# VA-Meter_Analog_Part.net
KiCad netlist of a schematic drawn in EAGLE
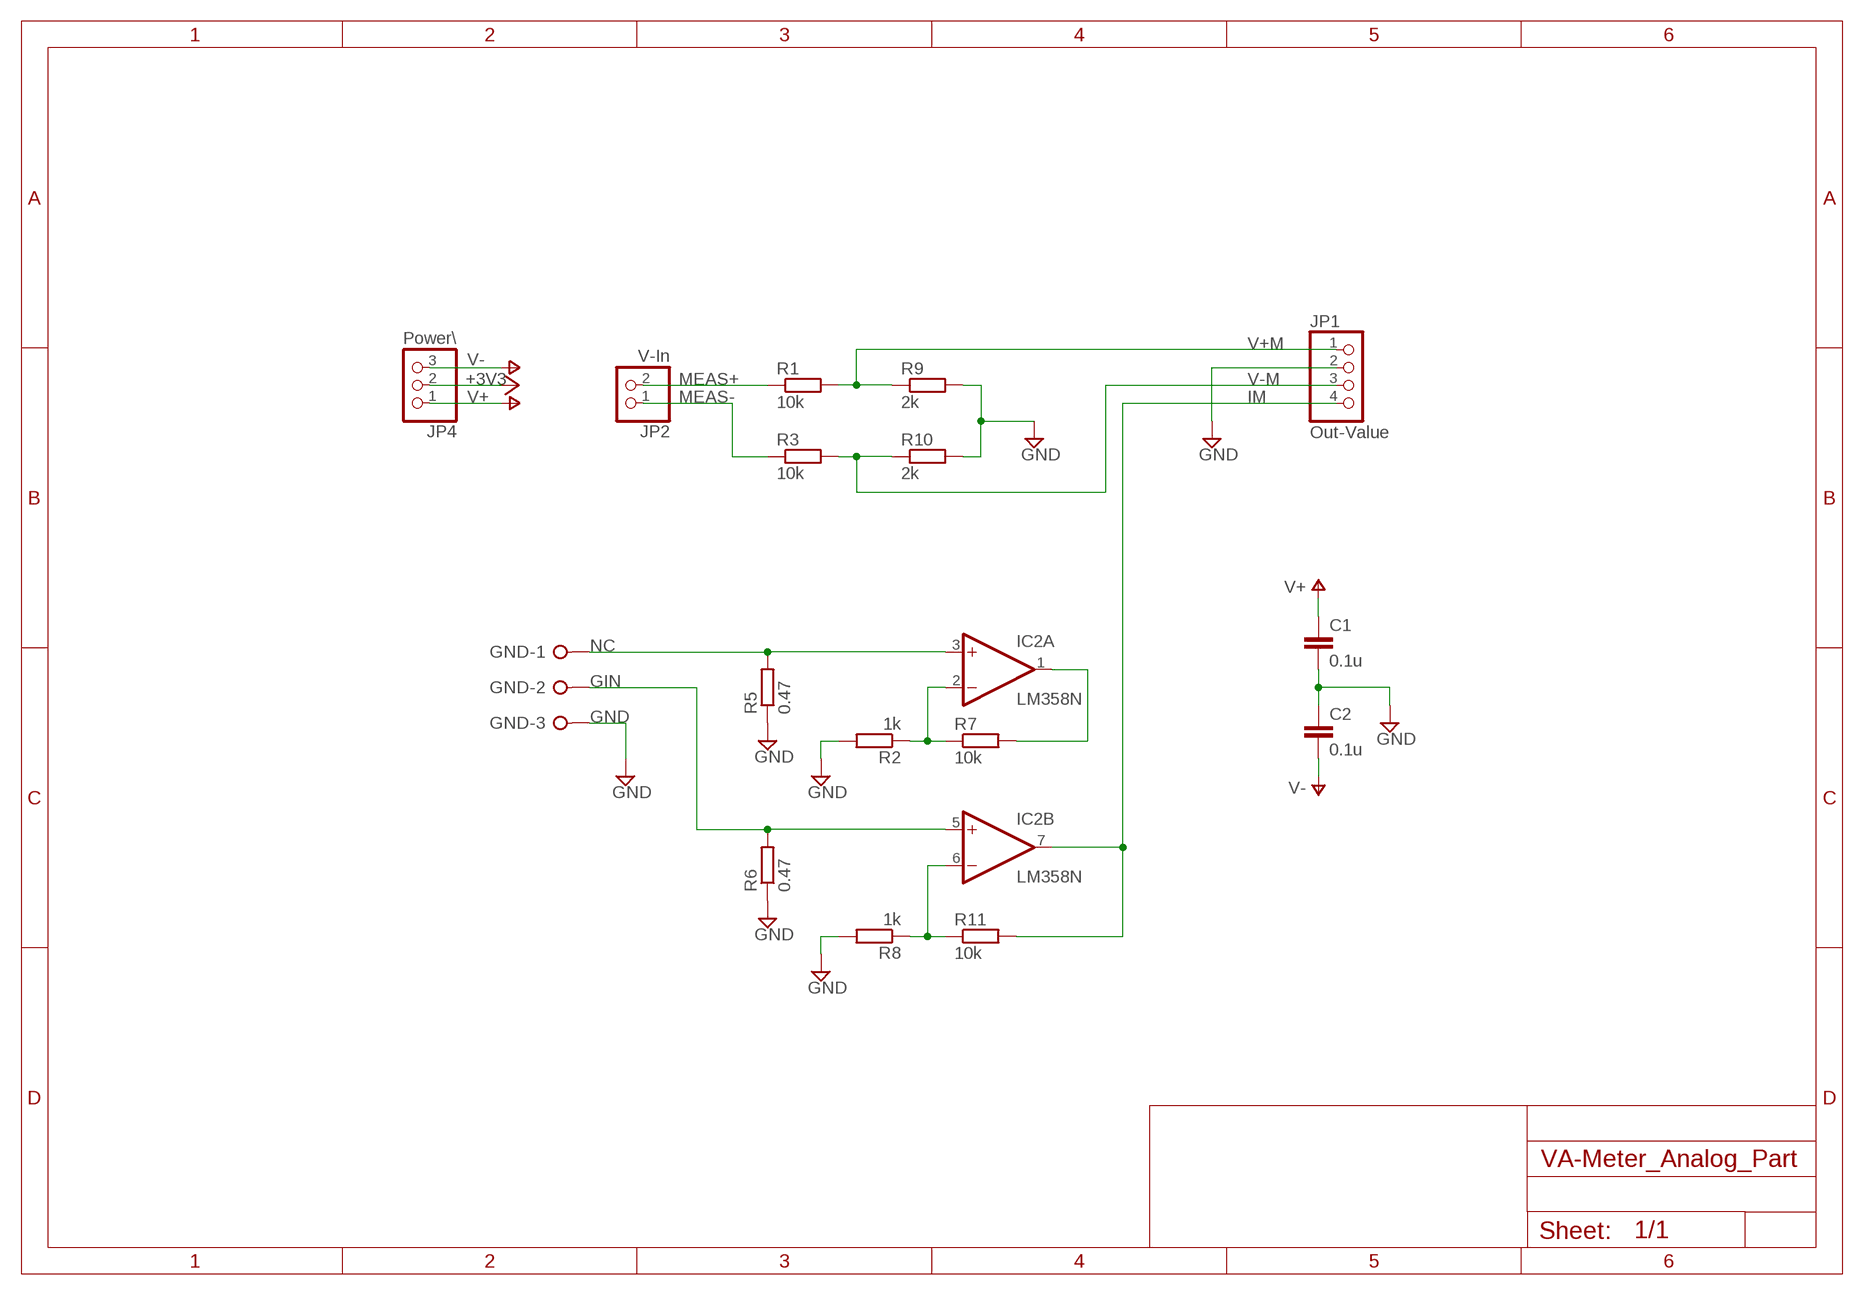
[diagram p0: schematic, sheet 1]

(export (version "E")
  (design (tool "Eeschema 10.0.6"))
  (components
    (comp (ref "C1")
      (value "0.1u")
      (footprint "eagle-import:C050-024X044")
      (libsource (lib "eagle-import") (part "C-EU050-024X044"))
    )
    (comp (ref "C2")
      (value "0.1u")
      (footprint "eagle-import:C050-024X044")
      (libsource (lib "eagle-import") (part "C-EU050-024X044"))
    )
    (comp (ref "GND")
      (value "W237-03P")
      (footprint "eagle-import:W237-133")
      (libsource (lib "eagle-import") (part "W237-03P"))
    )
    (comp (ref "IC2")
      (value "LM358N")
      (footprint "eagle-import:DIL08")
      (libsource (lib "eagle-import") (part "LM358N"))
    )
    (comp (ref "JP1")
      (value "Out-Value")
      (footprint "eagle-import:1X04")
      (libsource (lib "eagle-import") (part "PINHD-1X4"))
    )
    (comp (ref "JP2")
      (value "V-In")
      (footprint "eagle-import:1X02")
      (libsource (lib "eagle-import") (part "PINHD-1X2"))
    )
    (comp (ref "JP4")
      (value "Power\\")
      (footprint "eagle-import:1X03")
      (libsource (lib "eagle-import") (part "PINHD-1X3"))
    )
    (comp (ref "R1")
      (value "10k")
      (footprint "eagle-import:0207_7")
      (libsource (lib "eagle-import") (part "R-EU_0207/7"))
    )
    (comp (ref "R2")
      (value "1k")
      (footprint "eagle-import:0207_7")
      (libsource (lib "eagle-import") (part "R-EU_0207/7"))
    )
    (comp (ref "R3")
      (value "10k")
      (footprint "eagle-import:0207_7")
      (libsource (lib "eagle-import") (part "R-EU_0207/7"))
    )
    (comp (ref "R5")
      (value "0.47")
      (footprint "eagle-import:P0613_15")
      (libsource (lib "eagle-import") (part "R-EU_0613/15"))
    )
    (comp (ref "R6")
      (value "0.47")
      (footprint "eagle-import:P0613_15")
      (libsource (lib "eagle-import") (part "R-EU_0613/15"))
    )
    (comp (ref "R7")
      (value "10k")
      (footprint "eagle-import:0207_7")
      (libsource (lib "eagle-import") (part "R-EU_0207/7"))
    )
    (comp (ref "R8")
      (value "1k")
      (footprint "eagle-import:0207_7")
      (libsource (lib "eagle-import") (part "R-EU_0207/7"))
    )
    (comp (ref "R9")
      (value "2k")
      (footprint "eagle-import:0207_7")
      (libsource (lib "eagle-import") (part "R-EU_0207/7"))
    )
    (comp (ref "R10")
      (value "2k")
      (footprint "eagle-import:0207_7")
      (libsource (lib "eagle-import") (part "R-EU_0207/7"))
    )
    (comp (ref "R11")
      (value "10k")
      (footprint "eagle-import:0207_7")
      (libsource (lib "eagle-import") (part "R-EU_0207/7"))
    )
  )
  (nets
    (net (code "1") (name "+3V3") (class "Default")
      (node (ref "JP4") (pin "2") (pinfunction "2_2") (pintype "passive"))
    )
    (net (code "2") (name "/GIN") (class "Default")
      (node (ref "GND") (pin "2") (pinfunction "KL_2") (pintype "passive"))
      (node (ref "IC2") (pin "5") (pinfunction "+IN_5") (pintype "input"))
      (node (ref "R6") (pin "2") (pinfunction "2_2") (pintype "passive"))
    )
    (net (code "3") (name "/IM") (class "Default")
      (node (ref "IC2") (pin "7") (pinfunction "OUT_7") (pintype "output"))
      (node (ref "JP1") (pin "4") (pinfunction "4_4") (pintype "passive"))
      (node (ref "R11") (pin "2") (pinfunction "2_2") (pintype "passive"))
    )
    (net (code "4") (name "/MEAS+") (class "Default")
      (node (ref "JP2") (pin "2") (pinfunction "2_2") (pintype "passive"))
      (node (ref "R1") (pin "1") (pinfunction "1_1") (pintype "passive"))
    )
    (net (code "5") (name "/MEAS-") (class "Default")
      (node (ref "JP2") (pin "1") (pinfunction "1_1") (pintype "passive"))
      (node (ref "R3") (pin "1") (pinfunction "1_1") (pintype "passive"))
    )
    (net (code "6") (name "/NC") (class "Default")
      (node (ref "GND") (pin "1") (pinfunction "KL_1") (pintype "passive"))
      (node (ref "IC2") (pin "3") (pinfunction "+IN_3") (pintype "input"))
      (node (ref "R5") (pin "2") (pinfunction "2_2") (pintype "passive"))
    )
    (net (code "7") (name "/V+M") (class "Default")
      (node (ref "JP1") (pin "1") (pinfunction "1_1") (pintype "passive"))
      (node (ref "R1") (pin "2") (pinfunction "2_2") (pintype "passive"))
      (node (ref "R9") (pin "1") (pinfunction "1_1") (pintype "passive"))
    )
    (net (code "8") (name "/V-M") (class "Default")
      (node (ref "JP1") (pin "3") (pinfunction "3_3") (pintype "passive"))
      (node (ref "R10") (pin "1") (pinfunction "1_1") (pintype "passive"))
      (node (ref "R3") (pin "2") (pinfunction "2_2") (pintype "passive"))
    )
    (net (code "9") (name "GND") (class "Default")
      (node (ref "C1") (pin "2") (pinfunction "2_2") (pintype "passive"))
      (node (ref "C2") (pin "1") (pinfunction "1_1") (pintype "passive"))
      (node (ref "GND") (pin "3") (pinfunction "KL_3") (pintype "passive"))
      (node (ref "JP1") (pin "2") (pinfunction "2_2") (pintype "passive"))
      (node (ref "R10") (pin "2") (pinfunction "2_2") (pintype "passive"))
      (node (ref "R2") (pin "2") (pinfunction "2_2") (pintype "passive"))
      (node (ref "R5") (pin "1") (pinfunction "1_1") (pintype "passive"))
      (node (ref "R6") (pin "1") (pinfunction "1_1") (pintype "passive"))
      (node (ref "R8") (pin "2") (pinfunction "2_2") (pintype "passive"))
      (node (ref "R9") (pin "2") (pinfunction "2_2") (pintype "passive"))
    )
    (net (code "10") (name "Net-(IC2A--IN)") (class "Default")
      (node (ref "IC2") (pin "2") (pinfunction "-IN_2") (pintype "input"))
      (node (ref "R2") (pin "1") (pinfunction "1_1") (pintype "passive"))
      (node (ref "R7") (pin "1") (pinfunction "1_1") (pintype "passive"))
    )
    (net (code "11") (name "Net-(IC2A-OUT)") (class "Default")
      (node (ref "IC2") (pin "1") (pinfunction "OUT_1") (pintype "output"))
      (node (ref "R7") (pin "2") (pinfunction "2_2") (pintype "passive"))
    )
    (net (code "12") (name "Net-(IC2B--IN)") (class "Default")
      (node (ref "IC2") (pin "6") (pinfunction "-IN_6") (pintype "input"))
      (node (ref "R11") (pin "1") (pinfunction "1_1") (pintype "passive"))
      (node (ref "R8") (pin "1") (pinfunction "1_1") (pintype "passive"))
    )
    (net (code "13") (name "V+") (class "Default")
      (node (ref "C1") (pin "1") (pinfunction "1_1") (pintype "passive"))
      (node (ref "JP4") (pin "1") (pinfunction "1_1") (pintype "passive"))
    )
    (net (code "14") (name "V-") (class "Default")
      (node (ref "C2") (pin "2") (pinfunction "2_2") (pintype "passive"))
      (node (ref "JP4") (pin "3") (pinfunction "3_3") (pintype "passive"))
    )
  )
)
